# ttd.net
KiCad netlist of a schematic drawn in EAGLE
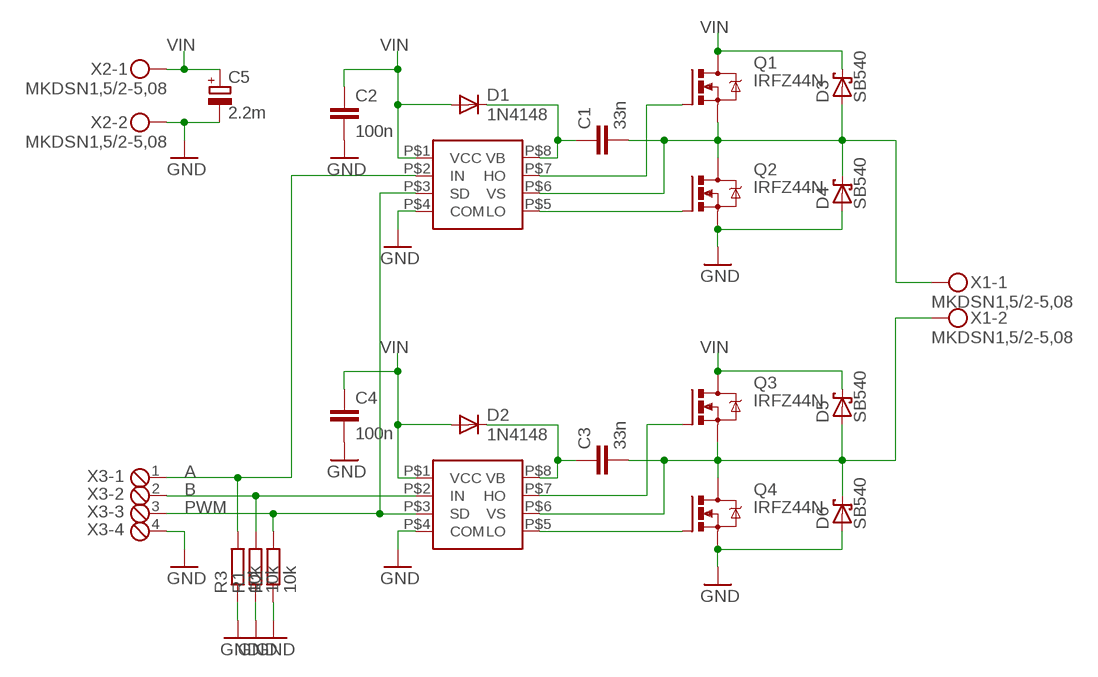
[diagram p0: schematic, sheet 1]

(export (version "E")
  (design (tool "Eeschema 10.0.6"))
  (components
    (comp (ref "C1")
      (value "33n")
      (footprint "eagle-import:C050-025X075")
      (libsource (lib "eagle-import") (part "C-EU050-025X075"))
    )
    (comp (ref "C2")
      (value "100n")
      (footprint "eagle-import:C075-032X103")
      (libsource (lib "eagle-import") (part "resistor_C-EU075-032X103"))
    )
    (comp (ref "C3")
      (value "33n")
      (footprint "eagle-import:C050-025X075")
      (libsource (lib "eagle-import") (part "C-EU050-025X075"))
    )
    (comp (ref "C4")
      (value "100n")
      (footprint "eagle-import:C075-032X103")
      (libsource (lib "eagle-import") (part "resistor_C-EU075-032X103"))
    )
    (comp (ref "C5")
      (value "2.2m")
      (footprint "eagle-import:E7,5-18")
      (libsource (lib "eagle-import") (part "CPOL-EUE7.5-18"))
    )
    (comp (ref "D1")
      (value "1N4148")
      (footprint "eagle-import:DO35-10")
      (libsource (lib "eagle-import") (part "1N4148DO35-10"))
    )
    (comp (ref "D2")
      (value "1N4148")
      (footprint "eagle-import:DO35-10")
      (libsource (lib "eagle-import") (part "1N4148DO35-10"))
    )
    (comp (ref "D3")
      (value "SB540")
      (footprint "eagle-import:DO201T15")
      (libsource (lib "eagle-import") (part "SCHOTTKY-DIODEDO201T15"))
    )
    (comp (ref "D4")
      (value "SB540")
      (footprint "eagle-import:DO201T15")
      (libsource (lib "eagle-import") (part "SCHOTTKY-DIODEDO201T15"))
    )
    (comp (ref "D5")
      (value "SB540")
      (footprint "eagle-import:DO201T15")
      (libsource (lib "eagle-import") (part "SCHOTTKY-DIODEDO201T15"))
    )
    (comp (ref "D6")
      (value "SB540")
      (footprint "eagle-import:DO201T15")
      (libsource (lib "eagle-import") (part "SCHOTTKY-DIODEDO201T15"))
    )
    (comp (ref "Q1")
      (value "IRFZ44N")
      (footprint "eagle-import:TO220BV")
      (libsource (lib "eagle-import") (part "IRF540"))
    )
    (comp (ref "Q2")
      (value "IRFZ44N")
      (footprint "eagle-import:TO220BV")
      (libsource (lib "eagle-import") (part "IRF540"))
    )
    (comp (ref "Q3")
      (value "IRFZ44N")
      (footprint "eagle-import:TO220BV")
      (libsource (lib "eagle-import") (part "IRF540"))
    )
    (comp (ref "Q4")
      (value "IRFZ44N")
      (footprint "eagle-import:TO220BV")
      (libsource (lib "eagle-import") (part "IRF540"))
    )
    (comp (ref "R1")
      (value "10k")
      (footprint "eagle-import:0207_7")
      (libsource (lib "eagle-import") (part "R-EU_0207/7"))
    )
    (comp (ref "R2")
      (value "10k")
      (footprint "eagle-import:0207_7")
      (libsource (lib "eagle-import") (part "R-EU_0207/7"))
    )
    (comp (ref "R3")
      (value "10k")
      (footprint "eagle-import:0207_10")
      (libsource (lib "eagle-import") (part "R-EU_0207/10"))
    )
    (comp (ref "U$1")
      (value "IR2104")
      (footprint "eagle-import:IR2104_DIL")
      (libsource (lib "eagle-import") (part "IR2104"))
    )
    (comp (ref "U$2")
      (value "IR2104")
      (footprint "eagle-import:IR2104_DIL")
      (libsource (lib "eagle-import") (part "IR2104"))
    )
    (comp (ref "X1")
      (value "MKDSN1,5/2-5,08")
      (footprint "eagle-import:MKDSN1,5_2-5,08")
      (fields (field (name "MPN") "MKDSN 1,5/2-5.08"))
      (libsource (lib "eagle-import") (part "MKDSN1,5/2-5,08"))
    )
    (comp (ref "X2")
      (value "MKDSN1,5/2-5,08")
      (footprint "eagle-import:MKDSN1,5_2-5,08")
      (fields (field (name "MPN") "MKDSN 1,5/2-5.08"))
      (libsource (lib "eagle-import") (part "MKDSN1,5/2-5,08"))
    )
    (comp (ref "X3")
      (value "MPT4")
      (footprint "eagle-import:4POL254")
      (libsource (lib "eagle-import") (part "MPT4"))
    )
  )
  (nets
    (net (code "1") (name "/A") (class "Default")
      (node (ref "R3") (pin "2") (pinfunction "2_2") (pintype "passive"))
      (node (ref "U$1") (pin "P$2") (pinfunction "IN_P$2") (pintype "bidirectional"))
      (node (ref "X3") (pin "1") (pinfunction "1_1") (pintype "passive"))
    )
    (net (code "2") (name "/B") (class "Default")
      (node (ref "R1") (pin "2") (pinfunction "2_2") (pintype "passive"))
      (node (ref "U$2") (pin "P$2") (pinfunction "IN_P$2") (pintype "bidirectional"))
      (node (ref "X3") (pin "2") (pinfunction "1_2") (pintype "passive"))
    )
    (net (code "3") (name "/PWM") (class "Default")
      (node (ref "R2") (pin "2") (pinfunction "2_2") (pintype "passive"))
      (node (ref "U$1") (pin "P$3") (pinfunction "SD_P$3") (pintype "bidirectional"))
      (node (ref "U$2") (pin "P$3") (pinfunction "SD_P$3") (pintype "bidirectional"))
      (node (ref "X3") (pin "3") (pinfunction "1_3") (pintype "passive"))
    )
    (net (code "4") (name "/VIN") (class "Default")
      (node (ref "C2") (pin "1") (pinfunction "1_1") (pintype "passive"))
      (node (ref "C4") (pin "1") (pinfunction "1_1") (pintype "passive"))
      (node (ref "C5") (pin "+") (pinfunction "+_+") (pintype "passive"))
      (node (ref "D1") (pin "A") (pinfunction "A_A") (pintype "passive"))
      (node (ref "D2") (pin "A") (pinfunction "A_A") (pintype "passive"))
      (node (ref "D3") (pin "C") (pinfunction "C_C") (pintype "passive"))
      (node (ref "D5") (pin "C") (pinfunction "C_C") (pintype "passive"))
      (node (ref "Q1") (pin "D") (pinfunction "D_D") (pintype "passive"))
      (node (ref "Q3") (pin "D") (pinfunction "D_D") (pintype "passive"))
      (node (ref "U$1") (pin "P$1") (pinfunction "VCC_P$1") (pintype "bidirectional"))
      (node (ref "U$2") (pin "P$1") (pinfunction "VCC_P$1") (pintype "bidirectional"))
      (node (ref "X2") (pin "1") (pinfunction "KL_1") (pintype "passive"))
    )
    (net (code "5") (name "GND") (class "Default")
      (node (ref "C2") (pin "2") (pinfunction "2_2") (pintype "passive"))
      (node (ref "C4") (pin "2") (pinfunction "2_2") (pintype "passive"))
      (node (ref "C5") (pin "-") (pinfunction "-_-") (pintype "passive"))
      (node (ref "D4") (pin "A") (pinfunction "A_A") (pintype "passive"))
      (node (ref "D6") (pin "A") (pinfunction "A_A") (pintype "passive"))
      (node (ref "Q2") (pin "S") (pinfunction "S_S") (pintype "passive"))
      (node (ref "Q4") (pin "S") (pinfunction "S_S") (pintype "passive"))
      (node (ref "R1") (pin "1") (pinfunction "1_1") (pintype "passive"))
      (node (ref "R2") (pin "1") (pinfunction "1_1") (pintype "passive"))
      (node (ref "R3") (pin "1") (pinfunction "1_1") (pintype "passive"))
      (node (ref "U$1") (pin "P$4") (pinfunction "COM_P$4") (pintype "bidirectional"))
      (node (ref "U$2") (pin "P$4") (pinfunction "COM_P$4") (pintype "bidirectional"))
      (node (ref "X2") (pin "2") (pinfunction "KL_2") (pintype "passive"))
      (node (ref "X3") (pin "4") (pinfunction "1_4") (pintype "passive"))
    )
    (net (code "6") (name "Net-(U$1-HO)") (class "Default")
      (node (ref "Q1") (pin "G") (pinfunction "G_G") (pintype "passive"))
      (node (ref "U$1") (pin "P$7") (pinfunction "HO_P$7") (pintype "bidirectional"))
    )
    (net (code "7") (name "Net-(U$1-LO)") (class "Default")
      (node (ref "Q2") (pin "G") (pinfunction "G_G") (pintype "passive"))
      (node (ref "U$1") (pin "P$5") (pinfunction "LO_P$5") (pintype "bidirectional"))
    )
    (net (code "8") (name "Net-(U$1-VB)") (class "Default")
      (node (ref "C1") (pin "1") (pinfunction "1_1") (pintype "passive"))
      (node (ref "D1") (pin "C") (pinfunction "C_C") (pintype "passive"))
      (node (ref "U$1") (pin "P$8") (pinfunction "VB_P$8") (pintype "bidirectional"))
    )
    (net (code "9") (name "Net-(U$1-VS)") (class "Default")
      (node (ref "C1") (pin "2") (pinfunction "2_2") (pintype "passive"))
      (node (ref "D3") (pin "A") (pinfunction "A_A") (pintype "passive"))
      (node (ref "D4") (pin "C") (pinfunction "C_C") (pintype "passive"))
      (node (ref "Q1") (pin "S") (pinfunction "S_S") (pintype "passive"))
      (node (ref "Q2") (pin "D") (pinfunction "D_D") (pintype "passive"))
      (node (ref "U$1") (pin "P$6") (pinfunction "VS_P$6") (pintype "bidirectional"))
      (node (ref "X1") (pin "1") (pinfunction "KL_1") (pintype "passive"))
    )
    (net (code "10") (name "Net-(U$2-HO)") (class "Default")
      (node (ref "Q3") (pin "G") (pinfunction "G_G") (pintype "passive"))
      (node (ref "U$2") (pin "P$7") (pinfunction "HO_P$7") (pintype "bidirectional"))
    )
    (net (code "11") (name "Net-(U$2-LO)") (class "Default")
      (node (ref "Q4") (pin "G") (pinfunction "G_G") (pintype "passive"))
      (node (ref "U$2") (pin "P$5") (pinfunction "LO_P$5") (pintype "bidirectional"))
    )
    (net (code "12") (name "Net-(U$2-VB)") (class "Default")
      (node (ref "C3") (pin "1") (pinfunction "1_1") (pintype "passive"))
      (node (ref "D2") (pin "C") (pinfunction "C_C") (pintype "passive"))
      (node (ref "U$2") (pin "P$8") (pinfunction "VB_P$8") (pintype "bidirectional"))
    )
    (net (code "13") (name "Net-(U$2-VS)") (class "Default")
      (node (ref "C3") (pin "2") (pinfunction "2_2") (pintype "passive"))
      (node (ref "D5") (pin "A") (pinfunction "A_A") (pintype "passive"))
      (node (ref "D6") (pin "C") (pinfunction "C_C") (pintype "passive"))
      (node (ref "Q3") (pin "S") (pinfunction "S_S") (pintype "passive"))
      (node (ref "Q4") (pin "D") (pinfunction "D_D") (pintype "passive"))
      (node (ref "U$2") (pin "P$6") (pinfunction "VS_P$6") (pintype "bidirectional"))
      (node (ref "X1") (pin "2") (pinfunction "KL_2") (pintype "passive"))
    )
  )
)
